# comunicacao.net
KiCad netlist of a schematic drawn in Altium Designer
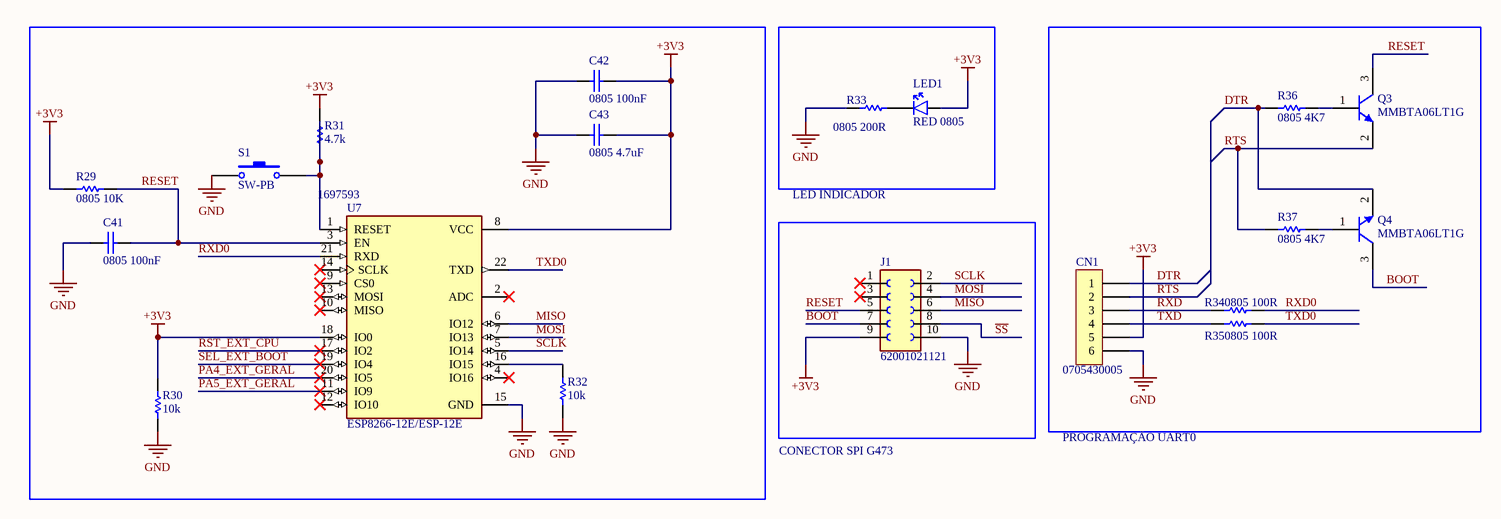
[diagram p0: comunicacao.SchDoc]

(export (version "E")
  (design (tool "Eeschema 10.0.6"))
  (components
    (comp (ref "C41")
      (value "0805 100nF")
      (footprint "CAP0805")
      (description "CC Series 0805 0.1 uF 50 V ±10 % Tolerance X7R SMT Multilayer Ceramic Capacitor")
      (fields
        (field (name "MANUFACTURER") "Yageo")
        (field (name "MANUFACTURER PART NUMBER") "CC0805KRX7R9BB104")
      )
      (libsource (lib "occhi") (part "CC0805KRX7R9BB104"))
    )
    (comp (ref "C42")
      (value "0805 100nF")
      (footprint "CAP0805")
      (description "CC Series 0805 0.1 uF 50 V ±10 % Tolerance X7R SMT Multilayer Ceramic Capacitor")
      (fields
        (field (name "MANUFACTURER") "Yageo")
        (field (name "MANUFACTURER PART NUMBER") "CC0805KRX7R9BB104")
      )
      (libsource (lib "occhi") (part "CC0805KRX7R9BB104"))
    )
    (comp (ref "C43")
      (value "0805 4.7uF")
      (footprint "CAP0805")
      (description "4.7uF ±10% 50V 0805")
      (fields
        (field (name "MANUFACTURER") "TDK")
        (field (name "MANUFACTURER PART NUMBER") "C2012X5R1H475K125AB")
      )
      (libsource (lib "occhi") (part "C2012X5R1H475K125AB"))
    )
    (comp (ref "CN1")
      (value "0705430005")
      (footprint "FP-0705430005-MFG")
      (description "Conn Shrouded Header (4 Sides) HDR 6 POS 2.54mm Solder ST Top Entry Thru-Hole SL™ Tube")
      (fields (field (name "MANUFACTURER") "Molex"))
      (libsource (lib "occhi") (part "0705430005"))
    )
    (comp (ref "J1")
      (value "62001021121")
      (footprint "62001021121")
      (fields (field (name "MF") "WÃ¼rth Elektronik"))
      (libsource (lib "62001021121") (part "62001021121"))
    )
    (comp (ref "LED1")
      (value "RED 0805")
      (footprint "LEDC2012X80N")
      (description "Red SMD 625nm LED Indication - Discrete 2V 0805 (2012 Metric)")
      (fields
        (field (name "MANUFACTURER_PART_NUMBER") "150080RS75000")
        (field (name "MOUSER PART NUMBER") "710-150080RS75000")
      )
      (libsource (lib "occhi") (part "150080RS75000"))
    )
    (comp (ref "Q3")
      (value "MMBTA06LT1G")
      (footprint "ONSC-SOT-23-3-318-08_V")
      (description "Trans GP BJT NPN 80V 0.5A 3-Pin SOT-23 T/R")
      (fields (field (name "MANUFACTURER") "ON Semiconductor"))
      (libsource (lib "occhi") (part "MMBTA06LT1G"))
    )
    (comp (ref "Q4")
      (value "MMBTA06LT1G")
      (footprint "ONSC-SOT-23-3-318-08_V")
      (description "Trans GP BJT NPN 80V 0.5A 3-Pin SOT-23 T/R")
      (fields (field (name "MANUFACTURER") "ON Semiconductor"))
      (libsource (lib "occhi") (part "MMBTA06LT1G"))
    )
    (comp (ref "R29")
      (value "0805 10K")
      (footprint "RES0805")
      (description "10K Omhs 0805 ± 1.00% 0.125W ± 100ppm/℃")
      (fields
        (field (name "MANUFACTURER") "Yageo")
        (field (name "MANUFACTURER PART NUMBER") "RC0603FR-0710KL")
      )
      (libsource (lib "occhi") (part "RC0805FR-0710KL"))
    )
    (comp (ref "R30")
      (value "10k")
      (footprint "R1608[0603]")
      (description "Res, 10K, 0.01%, 0.25W, 1206, Metal Foil")
      (fields (field (name "MANUFACTURER PART NUMBER") "Y163010K0000T9R") (field (name "TOLERANCE") "0.01%"))
      (libsource (lib "Basic Library") (part "R"))
    )
    (comp (ref "R31")
      (value "4.7k")
      (footprint "R1005[0402]")
      (description "Res Thick Film 1206 4.7K Ohm 5% 1/4W ±200ppm/°C Molded SMD Punched Carrier T/R")
      (fields (field (name "MANUFACTURER PART NUMBER") "ERJ-8GEYJ472V") (field (name "TOLERANCE") "5%"))
      (libsource (lib "Basic Library") (part "R"))
    )
    (comp (ref "R32")
      (value "10k")
      (footprint "R1608[0603]")
      (description "Res, 10K, 0.01%, 0.25W, 1206, Metal Foil")
      (fields (field (name "MANUFACTURER PART NUMBER") "Y163010K0000T9R") (field (name "TOLERANCE") "0.01%"))
      (libsource (lib "Basic Library") (part "R"))
    )
    (comp (ref "R33")
      (value "0805 200R")
      (footprint "RES0805")
      (description "200 Ohm  0805 ± 1.00% 0.125W ± 100ppm/℃")
      (fields
        (field (name "MANUFACTURER") "Yageo")
        (field (name "MANUFACTURER PART NUMBER") "RC0603FR-07200RL")
      )
      (libsource (lib "occhi") (part "RC0805FR-07200RL"))
    )
    (comp (ref "R34")
      (value "0805 100R")
      (footprint "RES0805")
      (description "100R ± 1.00% 0.125W ± 100ppm/℃ 0805")
      (fields
        (field (name "MANUFACTURER") "Yageo")
        (field (name "MANUFACTURER PART NUMBER") "RC0805FR-07100RL")
      )
      (libsource (lib "occhi") (part "RC0805FR-07100RL"))
    )
    (comp (ref "R35")
      (value "0805 100R")
      (footprint "RES0805")
      (description "100R ± 1.00% 0.125W ± 100ppm/℃ 0805")
      (fields
        (field (name "MANUFACTURER") "Yageo")
        (field (name "MANUFACTURER PART NUMBER") "RC0805FR-07100RL")
      )
      (libsource (lib "occhi") (part "RC0805FR-07100RL"))
    )
    (comp (ref "R36")
      (value "0805 4K7")
      (footprint "RES0805")
      (description "4700Ω ± 1.00% 0.125W ± 100ppm/℃ 0805")
      (fields
        (field (name "MANUFACTURER") "Yageo")
        (field (name "MANUFACTURER PART NUMBER") "RC0805FR-074K7L")
      )
      (libsource (lib "occhi") (part "RC0805FR-074K7L"))
    )
    (comp (ref "R37")
      (value "0805 4K7")
      (footprint "RES0805")
      (description "4700Ω ± 1.00% 0.125W ± 100ppm/℃ 0805")
      (fields
        (field (name "MANUFACTURER") "Yageo")
        (field (name "MANUFACTURER PART NUMBER") "RC0805FR-074K7L")
      )
      (libsource (lib "occhi") (part "RC0805FR-074K7L"))
    )
    (comp (ref "S1")
      (value "SW-PB")
      (footprint "PB-SW")
      (description "Tactile Switch")
      (libsource (lib "Basic Library") (part "SW Tact"))
    )
    (comp (ref "U7")
      (value "ESP8266-12E/ESP-12E")
      (footprint "XCVR_ESP8266-12E/ESP-12E")
      (fields (field (name "MF") "AI-Thinker") (field (name "SUPPLIER PART NUMBER 1") "1697593"))
      (libsource (lib "ESP8266-12E_ESP-12E") (part "ESP8266-12E/ESP-12E"))
    )
  )
  (nets
    (net (code "1") (name "+3V3") (class "Default")
      (node (ref "C42") (pin "2") (pinfunction "2_2") (pintype "passive"))
      (node (ref "C43") (pin "2") (pinfunction "2_2") (pintype "passive"))
      (node (ref "CN1") (pin "5") (pinfunction "5_5") (pintype "passive"))
      (node (ref "J1") (pin "9") (pinfunction "5_9") (pintype "passive"))
      (node (ref "LED1") (pin "2") (pinfunction "A_2") (pintype "passive"))
      (node (ref "R29") (pin "1") (pinfunction "1_1") (pintype "passive"))
      (node (ref "R30") (pin "2") (pinfunction "2_2") (pintype "passive"))
      (node (ref "R31") (pin "2") (pinfunction "2_2") (pintype "passive"))
      (node (ref "U7") (pin "18") (pinfunction "IO0_18") (pintype "bidirectional"))
      (node (ref "U7") (pin "8") (pinfunction "VCC_8") (pintype "power_in"))
    )
    (net (code "2") (name "/BOOT") (class "Default")
      (node (ref "J1") (pin "7") (pinfunction "4_7") (pintype "passive"))
      (node (ref "Q4") (pin "3") (pinfunction "C_3") (pintype "passive"))
    )
    (net (code "3") (name "/DTR") (class "Default")
      (node (ref "CN1") (pin "1") (pinfunction "1_1") (pintype "passive"))
      (node (ref "Q4") (pin "2") (pinfunction "E_2") (pintype "passive"))
      (node (ref "R36") (pin "1") (pinfunction "1_1") (pintype "passive"))
    )
    (net (code "4") (name "/MISO") (class "Default")
      (node (ref "J1") (pin "6") (pinfunction "8_6") (pintype "passive"))
      (node (ref "U7") (pin "6") (pinfunction "IO12_6") (pintype "bidirectional"))
    )
    (net (code "5") (name "/MOSI") (class "Default")
      (node (ref "J1") (pin "4") (pinfunction "9_4") (pintype "passive"))
      (node (ref "U7") (pin "7") (pinfunction "IO13_7") (pintype "bidirectional"))
    )
    (net (code "6") (name "/PA4_EXT_GERAL") (class "Default")
      (node (ref "U7") (pin "20") (pinfunction "IO5_20") (pintype "bidirectional+no_connect"))
    )
    (net (code "7") (name "/PA5_EXT_GERAL") (class "Default")
      (node (ref "U7") (pin "11") (pinfunction "IO9_11") (pintype "bidirectional+no_connect"))
    )
    (net (code "8") (name "/RESET") (class "Default")
      (node (ref "C41") (pin "2") (pinfunction "2_2") (pintype "passive"))
      (node (ref "J1") (pin "5") (pinfunction "3_5") (pintype "passive"))
      (node (ref "Q3") (pin "3") (pinfunction "C_3") (pintype "passive"))
      (node (ref "R29") (pin "2") (pinfunction "2_2") (pintype "passive"))
      (node (ref "U7") (pin "3") (pinfunction "EN_3") (pintype "input"))
    )
    (net (code "9") (name "/RST_EXT_CPU") (class "Default")
      (node (ref "U7") (pin "17") (pinfunction "IO2_17") (pintype "bidirectional+no_connect"))
    )
    (net (code "10") (name "/RTS") (class "Default")
      (node (ref "CN1") (pin "2") (pinfunction "2_2") (pintype "passive"))
      (node (ref "Q3") (pin "2") (pinfunction "E_2") (pintype "passive"))
      (node (ref "R37") (pin "1") (pinfunction "1_1") (pintype "passive"))
    )
    (net (code "11") (name "/RXD") (class "Default")
      (node (ref "CN1") (pin "3") (pinfunction "3_3") (pintype "passive"))
      (node (ref "R34") (pin "1") (pinfunction "1_1") (pintype "passive"))
    )
    (net (code "12") (name "/RXD0") (class "Default")
      (node (ref "R34") (pin "2") (pinfunction "2_2") (pintype "passive"))
      (node (ref "U7") (pin "21") (pinfunction "RXD_21") (pintype "input"))
    )
    (net (code "13") (name "/SCLK") (class "Default")
      (node (ref "J1") (pin "2") (pinfunction "10_2") (pintype "passive"))
      (node (ref "U7") (pin "5") (pinfunction "IO14_5") (pintype "bidirectional"))
    )
    (net (code "14") (name "/SEL_EXT_BOOT") (class "Default")
      (node (ref "U7") (pin "19") (pinfunction "IO4_19") (pintype "bidirectional+no_connect"))
    )
    (net (code "15") (name "/TXD") (class "Default")
      (node (ref "CN1") (pin "4") (pinfunction "4_4") (pintype "passive"))
      (node (ref "R35") (pin "1") (pinfunction "1_1") (pintype "passive"))
    )
    (net (code "16") (name "/TXD0") (class "Default")
      (node (ref "R35") (pin "2") (pinfunction "2_2") (pintype "passive"))
      (node (ref "U7") (pin "22") (pinfunction "TXD_22") (pintype "output"))
    )
    (net (code "17") (name "/~{SS}") (class "Default")
      (node (ref "J1") (pin "8") (pinfunction "7_8") (pintype "passive"))
    )
    (net (code "18") (name "GND") (class "Default")
      (node (ref "C41") (pin "1") (pinfunction "1_1") (pintype "passive"))
      (node (ref "C42") (pin "1") (pinfunction "1_1") (pintype "passive"))
      (node (ref "C43") (pin "1") (pinfunction "1_1") (pintype "passive"))
      (node (ref "CN1") (pin "6") (pinfunction "6_6") (pintype "passive"))
      (node (ref "J1") (pin "10") (pinfunction "6_10") (pintype "passive"))
      (node (ref "R30") (pin "1") (pinfunction "1_1") (pintype "passive"))
      (node (ref "R32") (pin "1") (pinfunction "1_1") (pintype "passive"))
      (node (ref "R33") (pin "1") (pinfunction "1_1") (pintype "passive"))
      (node (ref "S1") (pin "1") (pinfunction "1_1") (pintype "passive"))
      (node (ref "U7") (pin "15") (pinfunction "GND_15") (pintype "power_in"))
    )
    (net (code "19") (name "Net-(LED1-K)") (class "Default")
      (node (ref "LED1") (pin "1") (pinfunction "K_1") (pintype "passive"))
      (node (ref "R33") (pin "2") (pinfunction "2_2") (pintype "passive"))
    )
    (net (code "20") (name "Net-(Q3-B)") (class "Default")
      (node (ref "Q3") (pin "1") (pinfunction "B_1") (pintype "passive"))
      (node (ref "R36") (pin "2") (pinfunction "2_2") (pintype "passive"))
    )
    (net (code "21") (name "Net-(Q4-B)") (class "Default")
      (node (ref "Q4") (pin "1") (pinfunction "B_1") (pintype "passive"))
      (node (ref "R37") (pin "2") (pinfunction "2_2") (pintype "passive"))
    )
    (net (code "22") (name "Net-(U7-IO15)") (class "Default")
      (node (ref "R32") (pin "2") (pinfunction "2_2") (pintype "passive"))
      (node (ref "U7") (pin "16") (pinfunction "IO15_16") (pintype "bidirectional"))
    )
    (net (code "23") (name "Net-(U7-RESET)") (class "Default")
      (node (ref "R31") (pin "1") (pinfunction "1_1") (pintype "passive"))
      (node (ref "S1") (pin "2") (pinfunction "2_2") (pintype "passive"))
      (node (ref "U7") (pin "1") (pinfunction "RESET_1") (pintype "input"))
    )
    (net (code "24") (name "unconnected-(J1-2-Pad3)") (class "Default")
      (node (ref "J1") (pin "3") (pinfunction "2_3") (pintype "passive+no_connect"))
    )
    (net (code "25") (name "unconnected-(J1-Pad1)") (class "Default")
      (node (ref "J1") (pin "1") (pinfunction "1_1") (pintype "passive+no_connect"))
    )
    (net (code "26") (name "unconnected-(U7-ADC-Pad2)") (class "Default")
      (node (ref "U7") (pin "2") (pinfunction "ADC_2") (pintype "passive+no_connect"))
    )
    (net (code "27") (name "unconnected-(U7-CS0-Pad9)") (class "Default")
      (node (ref "U7") (pin "9") (pinfunction "CS0_9") (pintype "input+no_connect"))
    )
    (net (code "28") (name "unconnected-(U7-IO10-Pad12)") (class "Default")
      (node (ref "U7") (pin "12") (pinfunction "IO10_12") (pintype "bidirectional+no_connect"))
    )
    (net (code "29") (name "unconnected-(U7-IO16-Pad4)") (class "Default")
      (node (ref "U7") (pin "4") (pinfunction "IO16_4") (pintype "bidirectional+no_connect"))
    )
    (net (code "30") (name "unconnected-(U7-MISO-Pad10)") (class "Default")
      (node (ref "U7") (pin "10") (pinfunction "MISO_10") (pintype "bidirectional+no_connect"))
    )
    (net (code "31") (name "unconnected-(U7-MOSI-Pad13)") (class "Default")
      (node (ref "U7") (pin "13") (pinfunction "MOSI_13") (pintype "bidirectional+no_connect"))
    )
    (net (code "32") (name "unconnected-(U7-SCLK-Pad14)") (class "Default")
      (node (ref "U7") (pin "14") (pinfunction "SCLK_14") (pintype "input+no_connect"))
    )
  )
)
